# BaseBoard.net
KiCad netlist of a schematic drawn in EAGLE
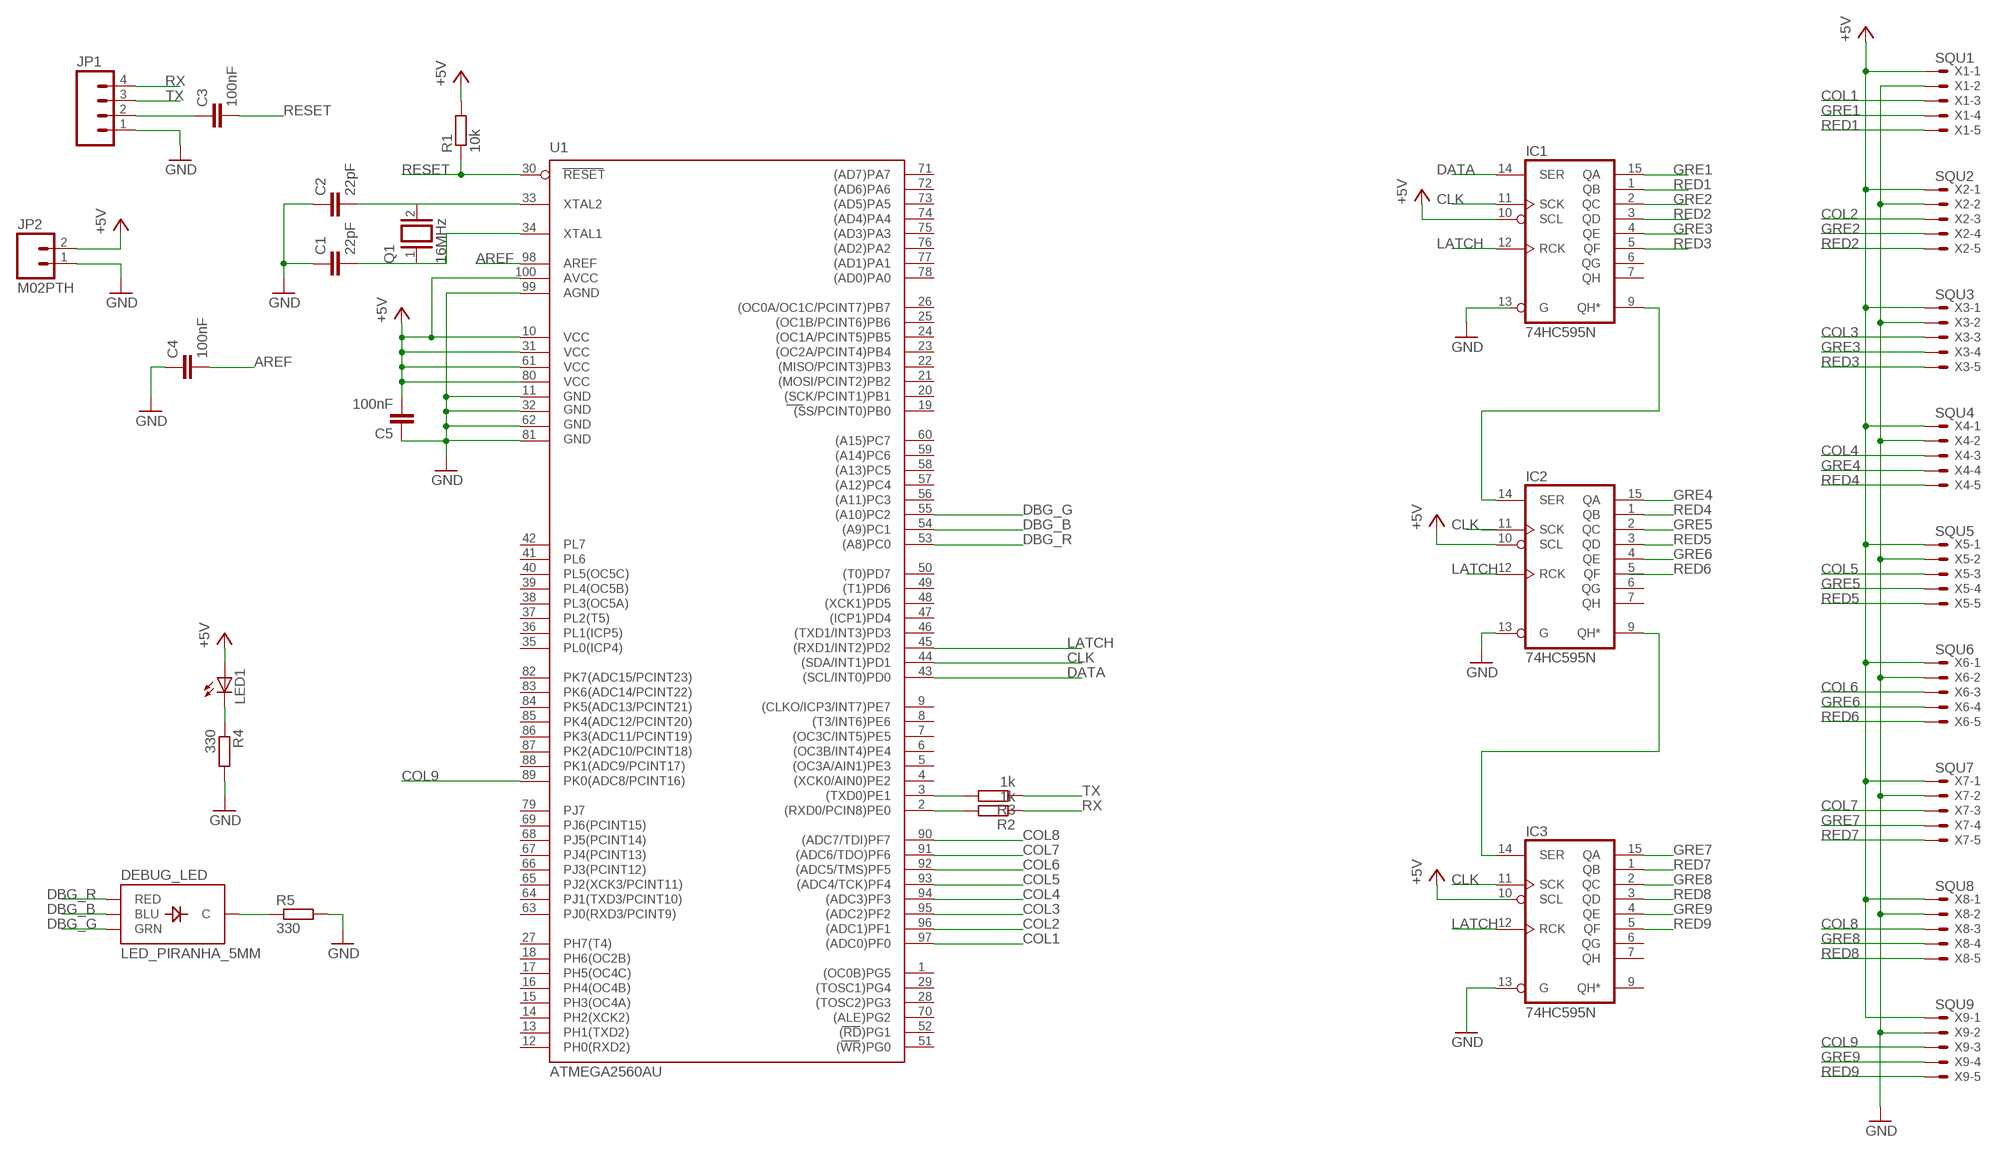
[diagram p0: schematic, sheet 1]

(export (version "E")
  (design (tool "Eeschema 10.0.6"))
  (components
    (comp (ref "C1")
      (value "22pF")
      (footprint "eagle-import:C5B2.5")
      (libsource (lib "eagle-import") (part "C5/2.5"))
    )
    (comp (ref "C2")
      (value "22pF")
      (footprint "eagle-import:C5B2.5")
      (libsource (lib "eagle-import") (part "C5/2.5"))
    )
    (comp (ref "C3")
      (value "100nF")
      (footprint "eagle-import:C5B3")
      (libsource (lib "eagle-import") (part "C5/3"))
    )
    (comp (ref "C4")
      (value "100nF")
      (footprint "eagle-import:C5B3")
      (libsource (lib "eagle-import") (part "C5/3"))
    )
    (comp (ref "C5")
      (value "100nF")
      (footprint "eagle-import:C5B3")
      (libsource (lib "eagle-import") (part "C5/3"))
    )
    (comp (ref "DEBUG_LED")
      (value "LED_PIRANHA_5MM")
      (footprint "eagle-import:LED_PIRANHA_5MM")
      (libsource (lib "eagle-import") (part "LED_PIRANHA_5MM"))
    )
    (comp (ref "IC1")
      (value "74HC595N")
      (footprint "eagle-import:DIL16")
      (libsource (lib "eagle-import") (part "74595NHC"))
    )
    (comp (ref "IC2")
      (value "74HC595N")
      (footprint "eagle-import:DIL16")
      (libsource (lib "eagle-import") (part "74595NHC"))
    )
    (comp (ref "IC3")
      (value "74HC595N")
      (footprint "eagle-import:DIL16")
      (libsource (lib "eagle-import") (part "74595NHC"))
    )
    (comp (ref "JP1")
      (value "M04PTH")
      (footprint "eagle-import:1X04")
      (libsource (lib "eagle-import") (part "M04PTH"))
    )
    (comp (ref "JP2")
      (value "M02PTH")
      (footprint "eagle-import:1X02")
      (libsource (lib "eagle-import") (part "M02PTH"))
    )
    (comp (ref "LED1")
      (value "LED3MM")
      (footprint "eagle-import:LED3MM")
      (libsource (lib "eagle-import") (part "LED3MM"))
    )
    (comp (ref "Q1")
      (value "16MHz")
      (footprint "eagle-import:QS")
      (libsource (lib "eagle-import") (part "XTAL/S"))
    )
    (comp (ref "R1")
      (value "10k")
      (footprint "eagle-import:0204_7")
      (libsource (lib "eagle-import") (part "R-EU_0204/7"))
    )
    (comp (ref "R2")
      (value "1k")
      (footprint "eagle-import:0204_7")
      (libsource (lib "eagle-import") (part "R-EU_0204/7"))
    )
    (comp (ref "R3")
      (value "1k")
      (footprint "eagle-import:0204_7")
      (libsource (lib "eagle-import") (part "R-EU_0204/7"))
    )
    (comp (ref "R4")
      (value "330")
      (footprint "eagle-import:0204_7")
      (libsource (lib "eagle-import") (part "R-EU_0204/7"))
    )
    (comp (ref "R5")
      (value "330")
      (footprint "eagle-import:0204_7")
      (libsource (lib "eagle-import") (part "R-EU_0204/7"))
    )
    (comp (ref "U1")
      (value "ATMEGA2560AU")
      (footprint "eagle-import:TQFP100")
      (libsource (lib "eagle-import") (part "ATMEGA2560AU"))
    )
    (comp (ref "X1")
      (value "SQU1")
      (footprint "eagle-import:53261-05")
      (libsource (lib "eagle-import") (part "53?-05261"))
    )
    (comp (ref "X2")
      (value "SQU2")
      (footprint "eagle-import:53261-05")
      (libsource (lib "eagle-import") (part "53?-05261"))
    )
    (comp (ref "X3")
      (value "SQU3")
      (footprint "eagle-import:53261-05")
      (libsource (lib "eagle-import") (part "53?-05261"))
    )
    (comp (ref "X4")
      (value "SQU4")
      (footprint "eagle-import:53261-05")
      (libsource (lib "eagle-import") (part "53?-05261"))
    )
    (comp (ref "X5")
      (value "SQU5")
      (footprint "eagle-import:53261-05")
      (libsource (lib "eagle-import") (part "53?-05261"))
    )
    (comp (ref "X6")
      (value "SQU6")
      (footprint "eagle-import:53261-05")
      (libsource (lib "eagle-import") (part "53?-05261"))
    )
    (comp (ref "X7")
      (value "SQU7")
      (footprint "eagle-import:53261-05")
      (libsource (lib "eagle-import") (part "53?-05261"))
    )
    (comp (ref "X8")
      (value "SQU8")
      (footprint "eagle-import:53261-05")
      (libsource (lib "eagle-import") (part "53?-05261"))
    )
    (comp (ref "X9")
      (value "SQU9")
      (footprint "eagle-import:53261-05")
      (libsource (lib "eagle-import") (part "53?-05261"))
    )
  )
  (nets
    (net (code "1") (name "+5V") (class "Default")
      (node (ref "C5") (pin "2") (pinfunction "2_2") (pintype "passive"))
      (node (ref "IC1") (pin "10") (pinfunction "SCL_10") (pintype "input"))
      (node (ref "IC2") (pin "10") (pinfunction "SCL_10") (pintype "input"))
      (node (ref "JP2") (pin "2") (pinfunction "2_2") (pintype "passive"))
      (node (ref "LED1") (pin "A") (pinfunction "A_A") (pintype "passive"))
      (node (ref "R1") (pin "2") (pinfunction "2_2") (pintype "passive"))
      (node (ref "U1") (pin "10") (pinfunction "VCC_10") (pintype "power_in"))
      (node (ref "U1") (pin "100") (pinfunction "AVCC_100") (pintype "power_in"))
      (node (ref "U1") (pin "31") (pinfunction "VCC1_31") (pintype "power_in"))
      (node (ref "U1") (pin "61") (pinfunction "VCC2_61") (pintype "power_in"))
      (node (ref "U1") (pin "80") (pinfunction "VCC3_80") (pintype "power_in"))
      (node (ref "X1") (pin "1") (pinfunction "S_1") (pintype "passive"))
      (node (ref "X2") (pin "1") (pinfunction "S_1") (pintype "passive"))
      (node (ref "X3") (pin "1") (pinfunction "S_1") (pintype "passive"))
      (node (ref "X4") (pin "1") (pinfunction "S_1") (pintype "passive"))
      (node (ref "X5") (pin "1") (pinfunction "S_1") (pintype "passive"))
      (node (ref "X6") (pin "1") (pinfunction "S_1") (pintype "passive"))
      (node (ref "X7") (pin "1") (pinfunction "S_1") (pintype "passive"))
      (node (ref "X8") (pin "1") (pinfunction "S_1") (pintype "passive"))
      (node (ref "X9") (pin "1") (pinfunction "S_1") (pintype "passive"))
    )
    (net (code "2") (name "/AREF") (class "Default")
      (node (ref "C4") (pin "2") (pinfunction "2_2") (pintype "passive"))
      (node (ref "U1") (pin "98") (pinfunction "AREF_98") (pintype "bidirectional"))
    )
    (net (code "3") (name "/CLK") (class "Default")
      (node (ref "IC1") (pin "11") (pinfunction "SCK_11") (pintype "input"))
      (node (ref "IC2") (pin "11") (pinfunction "SCK_11") (pintype "input"))
      (node (ref "IC3") (pin "11") (pinfunction "SCK_11") (pintype "input"))
      (node (ref "U1") (pin "44") (pinfunction "(SDA/INT1)PD1_44") (pintype "bidirectional"))
    )
    (net (code "4") (name "/COL1") (class "Default")
      (node (ref "U1") (pin "97") (pinfunction "(ADC0)PF0_97") (pintype "bidirectional"))
      (node (ref "X1") (pin "3") (pinfunction "S_3") (pintype "passive"))
    )
    (net (code "5") (name "/COL2") (class "Default")
      (node (ref "U1") (pin "96") (pinfunction "(ADC1)PF1_96") (pintype "bidirectional"))
      (node (ref "X2") (pin "3") (pinfunction "S_3") (pintype "passive"))
    )
    (net (code "6") (name "/COL3") (class "Default")
      (node (ref "U1") (pin "95") (pinfunction "(ADC2)PF2_95") (pintype "bidirectional"))
      (node (ref "X3") (pin "3") (pinfunction "S_3") (pintype "passive"))
    )
    (net (code "7") (name "/COL4") (class "Default")
      (node (ref "U1") (pin "94") (pinfunction "(ADC3)PF3_94") (pintype "bidirectional"))
      (node (ref "X4") (pin "3") (pinfunction "S_3") (pintype "passive"))
    )
    (net (code "8") (name "/COL5") (class "Default")
      (node (ref "U1") (pin "93") (pinfunction "(ADC4/TCK)PF4_93") (pintype "bidirectional"))
      (node (ref "X5") (pin "3") (pinfunction "S_3") (pintype "passive"))
    )
    (net (code "9") (name "/COL6") (class "Default")
      (node (ref "U1") (pin "92") (pinfunction "(ADC5/TMS)PF5_92") (pintype "bidirectional"))
      (node (ref "X6") (pin "3") (pinfunction "S_3") (pintype "passive"))
    )
    (net (code "10") (name "/COL7") (class "Default")
      (node (ref "U1") (pin "91") (pinfunction "(ADC6/TDO)PF6_91") (pintype "bidirectional"))
      (node (ref "X7") (pin "3") (pinfunction "S_3") (pintype "passive"))
    )
    (net (code "11") (name "/COL8") (class "Default")
      (node (ref "U1") (pin "90") (pinfunction "(ADC7/TDI)PF7_90") (pintype "bidirectional"))
      (node (ref "X8") (pin "3") (pinfunction "S_3") (pintype "passive"))
    )
    (net (code "12") (name "/COL9") (class "Default")
      (node (ref "U1") (pin "89") (pinfunction "PK0(ADC8/PCINT16)_89") (pintype "bidirectional"))
      (node (ref "X9") (pin "3") (pinfunction "S_3") (pintype "passive"))
    )
    (net (code "13") (name "/DATA") (class "Default")
      (node (ref "IC1") (pin "14") (pinfunction "SER_14") (pintype "input"))
      (node (ref "U1") (pin "43") (pinfunction "(SCL/INT0)PD0_43") (pintype "bidirectional"))
    )
    (net (code "14") (name "/DBG_B") (class "Default")
      (node (ref "DEBUG_LED") (pin "B") (pinfunction "BLU_B") (pintype "bidirectional"))
      (node (ref "U1") (pin "54") (pinfunction "(A9)PC1_54") (pintype "bidirectional"))
    )
    (net (code "15") (name "/DBG_G") (class "Default")
      (node (ref "DEBUG_LED") (pin "G") (pinfunction "GRN_G") (pintype "bidirectional"))
      (node (ref "U1") (pin "55") (pinfunction "(A10)PC2_55") (pintype "bidirectional"))
    )
    (net (code "16") (name "/DBG_R") (class "Default")
      (node (ref "DEBUG_LED") (pin "R") (pinfunction "RED_R") (pintype "bidirectional"))
      (node (ref "U1") (pin "53") (pinfunction "(A8)PC0_53") (pintype "bidirectional"))
    )
    (net (code "17") (name "/GRE1") (class "Default")
      (node (ref "IC1") (pin "15") (pinfunction "QA_15") (pintype "tri_state"))
      (node (ref "X1") (pin "4") (pinfunction "S_4") (pintype "passive"))
    )
    (net (code "18") (name "/GRE2") (class "Default")
      (node (ref "IC1") (pin "2") (pinfunction "QC_2") (pintype "tri_state"))
      (node (ref "X2") (pin "4") (pinfunction "S_4") (pintype "passive"))
    )
    (net (code "19") (name "/GRE3") (class "Default")
      (node (ref "IC1") (pin "4") (pinfunction "QE_4") (pintype "tri_state"))
      (node (ref "X3") (pin "4") (pinfunction "S_4") (pintype "passive"))
    )
    (net (code "20") (name "/GRE4") (class "Default")
      (node (ref "IC2") (pin "15") (pinfunction "QA_15") (pintype "tri_state"))
      (node (ref "X4") (pin "4") (pinfunction "S_4") (pintype "passive"))
    )
    (net (code "21") (name "/GRE5") (class "Default")
      (node (ref "IC2") (pin "2") (pinfunction "QC_2") (pintype "tri_state"))
      (node (ref "X5") (pin "4") (pinfunction "S_4") (pintype "passive"))
    )
    (net (code "22") (name "/GRE6") (class "Default")
      (node (ref "IC2") (pin "4") (pinfunction "QE_4") (pintype "tri_state"))
      (node (ref "X6") (pin "4") (pinfunction "S_4") (pintype "passive"))
    )
    (net (code "23") (name "/GRE7") (class "Default")
      (node (ref "IC3") (pin "15") (pinfunction "QA_15") (pintype "tri_state"))
      (node (ref "X7") (pin "4") (pinfunction "S_4") (pintype "passive"))
    )
    (net (code "24") (name "/GRE8") (class "Default")
      (node (ref "IC3") (pin "2") (pinfunction "QC_2") (pintype "tri_state"))
      (node (ref "X8") (pin "4") (pinfunction "S_4") (pintype "passive"))
    )
    (net (code "25") (name "/GRE9") (class "Default")
      (node (ref "IC3") (pin "4") (pinfunction "QE_4") (pintype "tri_state"))
      (node (ref "X9") (pin "4") (pinfunction "S_4") (pintype "passive"))
    )
    (net (code "26") (name "/LATCH") (class "Default")
      (node (ref "IC1") (pin "12") (pinfunction "RCK_12") (pintype "input"))
      (node (ref "IC2") (pin "12") (pinfunction "RCK_12") (pintype "input"))
      (node (ref "IC3") (pin "12") (pinfunction "RCK_12") (pintype "input"))
      (node (ref "U1") (pin "45") (pinfunction "(RXD1/INT2)PD2_45") (pintype "bidirectional"))
    )
    (net (code "27") (name "/RED1") (class "Default")
      (node (ref "IC1") (pin "1") (pinfunction "QB_1") (pintype "tri_state"))
      (node (ref "X1") (pin "5") (pinfunction "S_5") (pintype "passive"))
    )
    (net (code "28") (name "/RED2") (class "Default")
      (node (ref "IC1") (pin "3") (pinfunction "QD_3") (pintype "tri_state"))
      (node (ref "X2") (pin "5") (pinfunction "S_5") (pintype "passive"))
    )
    (net (code "29") (name "/RED3") (class "Default")
      (node (ref "IC1") (pin "5") (pinfunction "QF_5") (pintype "tri_state"))
      (node (ref "X3") (pin "5") (pinfunction "S_5") (pintype "passive"))
    )
    (net (code "30") (name "/RED4") (class "Default")
      (node (ref "IC2") (pin "1") (pinfunction "QB_1") (pintype "tri_state"))
      (node (ref "X4") (pin "5") (pinfunction "S_5") (pintype "passive"))
    )
    (net (code "31") (name "/RED5") (class "Default")
      (node (ref "IC2") (pin "3") (pinfunction "QD_3") (pintype "tri_state"))
      (node (ref "X5") (pin "5") (pinfunction "S_5") (pintype "passive"))
    )
    (net (code "32") (name "/RED6") (class "Default")
      (node (ref "X6") (pin "5") (pinfunction "S_5") (pintype "passive"))
    )
    (net (code "33") (name "/RED7") (class "Default")
      (node (ref "IC3") (pin "1") (pinfunction "QB_1") (pintype "tri_state"))
      (node (ref "X7") (pin "5") (pinfunction "S_5") (pintype "passive"))
    )
    (net (code "34") (name "/RED8") (class "Default")
      (node (ref "IC3") (pin "3") (pinfunction "QD_3") (pintype "tri_state"))
      (node (ref "X8") (pin "5") (pinfunction "S_5") (pintype "passive"))
    )
    (net (code "35") (name "/RED9") (class "Default")
      (node (ref "IC3") (pin "5") (pinfunction "QF_5") (pintype "tri_state"))
      (node (ref "X9") (pin "5") (pinfunction "S_5") (pintype "passive"))
    )
    (net (code "36") (name "/RESET") (class "Default")
      (node (ref "C3") (pin "2") (pinfunction "2_2") (pintype "passive"))
      (node (ref "R1") (pin "1") (pinfunction "1_1") (pintype "passive"))
      (node (ref "U1") (pin "30") (pinfunction "RESET_30") (pintype "input"))
    )
    (net (code "37") (name "/RX") (class "Default")
      (node (ref "JP1") (pin "4") (pinfunction "4_4") (pintype "passive"))
      (node (ref "R2") (pin "1") (pinfunction "1_1") (pintype "passive"))
    )
    (net (code "38") (name "/TX") (class "Default")
      (node (ref "JP1") (pin "3") (pinfunction "3_3") (pintype "passive"))
      (node (ref "R3") (pin "1") (pinfunction "1_1") (pintype "passive"))
    )
    (net (code "39") (name "GND") (class "Default")
      (node (ref "C1") (pin "1") (pinfunction "1_1") (pintype "passive"))
      (node (ref "C2") (pin "1") (pinfunction "1_1") (pintype "passive"))
      (node (ref "C4") (pin "1") (pinfunction "1_1") (pintype "passive"))
      (node (ref "C5") (pin "1") (pinfunction "1_1") (pintype "passive"))
      (node (ref "IC2") (pin "13") (pinfunction "G_13") (pintype "input"))
      (node (ref "JP1") (pin "1") (pinfunction "1_1") (pintype "passive"))
      (node (ref "JP2") (pin "1") (pinfunction "1_1") (pintype "passive"))
      (node (ref "R4") (pin "2") (pinfunction "2_2") (pintype "passive"))
      (node (ref "R5") (pin "2") (pinfunction "2_2") (pintype "passive"))
      (node (ref "U1") (pin "11") (pinfunction "GND_11") (pintype "power_in"))
      (node (ref "U1") (pin "32") (pinfunction "GND1_32") (pintype "power_in"))
      (node (ref "U1") (pin "62") (pinfunction "GND2_62") (pintype "power_in"))
      (node (ref "U1") (pin "81") (pinfunction "GND3_81") (pintype "power_in"))
      (node (ref "U1") (pin "99") (pinfunction "AGND_99") (pintype "power_in"))
      (node (ref "X1") (pin "2") (pinfunction "S_2") (pintype "passive"))
      (node (ref "X2") (pin "2") (pinfunction "S_2") (pintype "passive"))
      (node (ref "X3") (pin "2") (pinfunction "S_2") (pintype "passive"))
      (node (ref "X4") (pin "2") (pinfunction "S_2") (pintype "passive"))
      (node (ref "X5") (pin "2") (pinfunction "S_2") (pintype "passive"))
      (node (ref "X6") (pin "2") (pinfunction "S_2") (pintype "passive"))
      (node (ref "X7") (pin "2") (pinfunction "S_2") (pintype "passive"))
      (node (ref "X8") (pin "2") (pinfunction "S_2") (pintype "passive"))
      (node (ref "X9") (pin "2") (pinfunction "S_2") (pintype "passive"))
    )
    (net (code "40") (name "Net-(C3-Pad1)") (class "Default")
      (node (ref "C3") (pin "1") (pinfunction "1_1") (pintype "passive"))
      (node (ref "JP1") (pin "2") (pinfunction "2_2") (pintype "passive"))
    )
    (net (code "41") (name "Net-(DEBUG_LED-C)") (class "Default")
      (node (ref "DEBUG_LED") (pin "-") (pinfunction "C_-") (pintype "bidirectional"))
      (node (ref "R5") (pin "1") (pinfunction "1_1") (pintype "passive"))
    )
    (net (code "42") (name "Net-(IC1A-QH*)") (class "Default")
      (node (ref "IC1") (pin "9") (pinfunction "QH*_9") (pintype "tri_state"))
      (node (ref "IC2") (pin "14") (pinfunction "SER_14") (pintype "input"))
    )
    (net (code "43") (name "Net-(IC2A-QH*)") (class "Default")
      (node (ref "IC2") (pin "9") (pinfunction "QH*_9") (pintype "tri_state"))
      (node (ref "IC3") (pin "14") (pinfunction "SER_14") (pintype "input"))
    )
    (net (code "44") (name "Net-(LED1-C)") (class "Default")
      (node (ref "LED1") (pin "K") (pinfunction "C_K") (pintype "passive"))
      (node (ref "R4") (pin "1") (pinfunction "1_1") (pintype "passive"))
    )
    (net (code "45") (name "Net-(U1-(RXD0{slash}PCIN8)PE0)") (class "Default")
      (node (ref "R2") (pin "2") (pinfunction "2_2") (pintype "passive"))
      (node (ref "U1") (pin "2") (pinfunction "(RXD0/PCIN8)PE0_2") (pintype "bidirectional"))
    )
    (net (code "46") (name "Net-(U1-(TXD0)PE1)") (class "Default")
      (node (ref "R3") (pin "2") (pinfunction "2_2") (pintype "passive"))
      (node (ref "U1") (pin "3") (pinfunction "(TXD0)PE1_3") (pintype "bidirectional"))
    )
    (net (code "47") (name "Net-(U1-XTAL1)") (class "Default")
      (node (ref "C1") (pin "2") (pinfunction "2_2") (pintype "passive"))
      (node (ref "U1") (pin "34") (pinfunction "XTAL1_34") (pintype "input"))
    )
    (net (code "48") (name "Net-(U1-XTAL2)") (class "Default")
      (node (ref "C2") (pin "2") (pinfunction "2_2") (pintype "passive"))
      (node (ref "Q1") (pin "2") (pinfunction "2_2") (pintype "passive"))
      (node (ref "U1") (pin "33") (pinfunction "XTAL2_33") (pintype "output"))
    )
    (net (code "49") (name "unconnected-(IC1A-G-Pad13)") (class "Default")
      (node (ref "IC1") (pin "13") (pinfunction "G_13") (pintype "input"))
    )
    (net (code "50") (name "unconnected-(IC1A-QG-Pad6)") (class "Default")
      (node (ref "IC1") (pin "6") (pinfunction "QG_6") (pintype "tri_state"))
    )
    (net (code "51") (name "unconnected-(IC1A-QH-Pad7)") (class "Default")
      (node (ref "IC1") (pin "7") (pinfunction "QH_7") (pintype "tri_state"))
    )
    (net (code "52") (name "unconnected-(IC2A-QF-Pad5)") (class "Default")
      (node (ref "IC2") (pin "5") (pinfunction "QF_5") (pintype "tri_state"))
    )
    (net (code "53") (name "unconnected-(IC2A-QG-Pad6)") (class "Default")
      (node (ref "IC2") (pin "6") (pinfunction "QG_6") (pintype "tri_state"))
    )
    (net (code "54") (name "unconnected-(IC2A-QH-Pad7)") (class "Default")
      (node (ref "IC2") (pin "7") (pinfunction "QH_7") (pintype "tri_state"))
    )
    (net (code "55") (name "unconnected-(IC3A-G-Pad13)") (class "Default")
      (node (ref "IC3") (pin "13") (pinfunction "G_13") (pintype "input"))
    )
    (net (code "56") (name "unconnected-(IC3A-QG-Pad6)") (class "Default")
      (node (ref "IC3") (pin "6") (pinfunction "QG_6") (pintype "tri_state"))
    )
    (net (code "57") (name "unconnected-(IC3A-QH*-Pad9)") (class "Default")
      (node (ref "IC3") (pin "9") (pinfunction "QH*_9") (pintype "tri_state"))
    )
    (net (code "58") (name "unconnected-(IC3A-QH-Pad7)") (class "Default")
      (node (ref "IC3") (pin "7") (pinfunction "QH_7") (pintype "tri_state"))
    )
    (net (code "59") (name "unconnected-(IC3A-SCL-Pad10)") (class "Default")
      (node (ref "IC3") (pin "10") (pinfunction "SCL_10") (pintype "input"))
    )
    (net (code "60") (name "unconnected-(Q1-Pad1)") (class "Default")
      (node (ref "Q1") (pin "1") (pinfunction "1_1") (pintype "passive"))
    )
    (net (code "61") (name "unconnected-(U1-(A11)PC3-Pad56)") (class "Default")
      (node (ref "U1") (pin "56") (pinfunction "(A11)PC3_56") (pintype "bidirectional"))
    )
    (net (code "62") (name "unconnected-(U1-(A12)PC4-Pad57)") (class "Default")
      (node (ref "U1") (pin "57") (pinfunction "(A12)PC4_57") (pintype "bidirectional"))
    )
    (net (code "63") (name "unconnected-(U1-(A13)PC5-Pad58)") (class "Default")
      (node (ref "U1") (pin "58") (pinfunction "(A13)PC5_58") (pintype "bidirectional"))
    )
    (net (code "64") (name "unconnected-(U1-(A14)PC6-Pad59)") (class "Default")
      (node (ref "U1") (pin "59") (pinfunction "(A14)PC6_59") (pintype "bidirectional"))
    )
    (net (code "65") (name "unconnected-(U1-(A15)PC7-Pad60)") (class "Default")
      (node (ref "U1") (pin "60") (pinfunction "(A15)PC7_60") (pintype "bidirectional"))
    )
    (net (code "66") (name "unconnected-(U1-(AD0)PA0-Pad78)") (class "Default")
      (node (ref "U1") (pin "78") (pinfunction "(AD0)PA0_78") (pintype "bidirectional"))
    )
    (net (code "67") (name "unconnected-(U1-(AD1)PA1-Pad77)") (class "Default")
      (node (ref "U1") (pin "77") (pinfunction "(AD1)PA1_77") (pintype "bidirectional"))
    )
    (net (code "68") (name "unconnected-(U1-(AD2)PA2-Pad76)") (class "Default")
      (node (ref "U1") (pin "76") (pinfunction "(AD2)PA2_76") (pintype "bidirectional"))
    )
    (net (code "69") (name "unconnected-(U1-(AD3)PA3-Pad75)") (class "Default")
      (node (ref "U1") (pin "75") (pinfunction "(AD3)PA3_75") (pintype "bidirectional"))
    )
    (net (code "70") (name "unconnected-(U1-(AD4)PA4-Pad74)") (class "Default")
      (node (ref "U1") (pin "74") (pinfunction "(AD4)PA4_74") (pintype "bidirectional"))
    )
    (net (code "71") (name "unconnected-(U1-(AD5)PA5-Pad73)") (class "Default")
      (node (ref "U1") (pin "73") (pinfunction "(AD5)PA5_73") (pintype "bidirectional"))
    )
    (net (code "72") (name "unconnected-(U1-(AD6)PA6-Pad72)") (class "Default")
      (node (ref "U1") (pin "72") (pinfunction "(AD6)PA6_72") (pintype "bidirectional"))
    )
    (net (code "73") (name "unconnected-(U1-(AD7)PA7-Pad71)") (class "Default")
      (node (ref "U1") (pin "71") (pinfunction "(AD7)PA7_71") (pintype "bidirectional"))
    )
    (net (code "74") (name "unconnected-(U1-(ALE)PG2-Pad70)") (class "Default")
      (node (ref "U1") (pin "70") (pinfunction "(ALE)PG2_70") (pintype "bidirectional"))
    )
    (net (code "75") (name "unconnected-(U1-(CLKO{slash}ICP3{slash}INT7)PE7-Pad9)") (class "Default")
      (node (ref "U1") (pin "9") (pinfunction "(CLKO/ICP3/INT7)PE7_9") (pintype "bidirectional"))
    )
    (net (code "76") (name "unconnected-(U1-(ICP1)PD4-Pad47)") (class "Default")
      (node (ref "U1") (pin "47") (pinfunction "(ICP1)PD4_47") (pintype "bidirectional"))
    )
    (net (code "77") (name "unconnected-(U1-(MISO{slash}PCINT3)PB3-Pad22)") (class "Default")
      (node (ref "U1") (pin "22") (pinfunction "(MISO/PCINT3)PB3_22") (pintype "bidirectional"))
    )
    (net (code "78") (name "unconnected-(U1-(MOSI{slash}PCINT2)PB2-Pad21)") (class "Default")
      (node (ref "U1") (pin "21") (pinfunction "(MOSI/PCINT2)PB2_21") (pintype "bidirectional"))
    )
    (net (code "79") (name "unconnected-(U1-(OC0A{slash}OC1C{slash}PCINT7)PB7-Pad26)") (class "Default")
      (node (ref "U1") (pin "26") (pinfunction "(OC0A/OC1C/PCINT7)PB7_26") (pintype "bidirectional"))
    )
    (net (code "80") (name "unconnected-(U1-(OC0B)PG5-Pad1)") (class "Default")
      (node (ref "U1") (pin "1") (pinfunction "(OC0B)PG5_1") (pintype "bidirectional"))
    )
    (net (code "81") (name "unconnected-(U1-(OC1A{slash}PCINT5)PB5-Pad24)") (class "Default")
      (node (ref "U1") (pin "24") (pinfunction "(OC1A/PCINT5)PB5_24") (pintype "bidirectional"))
    )
    (net (code "82") (name "unconnected-(U1-(OC1B{slash}PCINT6)PB6-Pad25)") (class "Default")
      (node (ref "U1") (pin "25") (pinfunction "(OC1B/PCINT6)PB6_25") (pintype "bidirectional"))
    )
    (net (code "83") (name "unconnected-(U1-(OC2A{slash}PCINT4)PB4-Pad23)") (class "Default")
      (node (ref "U1") (pin "23") (pinfunction "(OC2A/PCINT4)PB4_23") (pintype "bidirectional"))
    )
    (net (code "84") (name "unconnected-(U1-(OC3A{slash}AIN1)PE3-Pad5)") (class "Default")
      (node (ref "U1") (pin "5") (pinfunction "(OC3A/AIN1)PE3_5") (pintype "bidirectional"))
    )
    (net (code "85") (name "unconnected-(U1-(OC3B{slash}INT4)PE4-Pad6)") (class "Default")
      (node (ref "U1") (pin "6") (pinfunction "(OC3B/INT4)PE4_6") (pintype "bidirectional"))
    )
    (net (code "86") (name "unconnected-(U1-(OC3C{slash}INT5)PE5-Pad7)") (class "Default")
      (node (ref "U1") (pin "7") (pinfunction "(OC3C/INT5)PE5_7") (pintype "bidirectional"))
    )
    (net (code "87") (name "unconnected-(U1-(RD)PG1-Pad52)") (class "Default")
      (node (ref "U1") (pin "52") (pinfunction "(RD)PG1_52") (pintype "bidirectional"))
    )
    (net (code "88") (name "unconnected-(U1-(SCK{slash}PCINT1)PB1-Pad20)") (class "Default")
      (node (ref "U1") (pin "20") (pinfunction "(SCK/PCINT1)PB1_20") (pintype "bidirectional"))
    )
    (net (code "89") (name "unconnected-(U1-(SS{slash}PCINT0)PB0-Pad19)") (class "Default")
      (node (ref "U1") (pin "19") (pinfunction "(SS/PCINT0)PB0_19") (pintype "bidirectional"))
    )
    (net (code "90") (name "unconnected-(U1-(T0)PD7-Pad50)") (class "Default")
      (node (ref "U1") (pin "50") (pinfunction "(T0)PD7_50") (pintype "bidirectional"))
    )
    (net (code "91") (name "unconnected-(U1-(T1)PD6-Pad49)") (class "Default")
      (node (ref "U1") (pin "49") (pinfunction "(T1)PD6_49") (pintype "bidirectional"))
    )
    (net (code "92") (name "unconnected-(U1-(T3{slash}INT6)PE6-Pad8)") (class "Default")
      (node (ref "U1") (pin "8") (pinfunction "(T3/INT6)PE6_8") (pintype "bidirectional"))
    )
    (net (code "93") (name "unconnected-(U1-(TOSC1)PG4-Pad29)") (class "Default")
      (node (ref "U1") (pin "29") (pinfunction "(TOSC1)PG4_29") (pintype "bidirectional"))
    )
    (net (code "94") (name "unconnected-(U1-(TOSC2)PG3-Pad28)") (class "Default")
      (node (ref "U1") (pin "28") (pinfunction "(TOSC2)PG3_28") (pintype "bidirectional"))
    )
    (net (code "95") (name "unconnected-(U1-(TXD1{slash}INT3)PD3-Pad46)") (class "Default")
      (node (ref "U1") (pin "46") (pinfunction "(TXD1/INT3)PD3_46") (pintype "bidirectional"))
    )
    (net (code "96") (name "unconnected-(U1-(WR)PG0-Pad51)") (class "Default")
      (node (ref "U1") (pin "51") (pinfunction "(WR)PG0_51") (pintype "bidirectional"))
    )
    (net (code "97") (name "unconnected-(U1-(XCK0{slash}AIN0)PE2-Pad4)") (class "Default")
      (node (ref "U1") (pin "4") (pinfunction "(XCK0/AIN0)PE2_4") (pintype "bidirectional"))
    )
    (net (code "98") (name "unconnected-(U1-(XCK1)PD5-Pad48)") (class "Default")
      (node (ref "U1") (pin "48") (pinfunction "(XCK1)PD5_48") (pintype "bidirectional"))
    )
    (net (code "99") (name "unconnected-(U1-PH0(RXD2)-Pad12)") (class "Default")
      (node (ref "U1") (pin "12") (pinfunction "PH0(RXD2)_12") (pintype "bidirectional"))
    )
    (net (code "100") (name "unconnected-(U1-PH1(TXD2)-Pad13)") (class "Default")
      (node (ref "U1") (pin "13") (pinfunction "PH1(TXD2)_13") (pintype "bidirectional"))
    )
    (net (code "101") (name "unconnected-(U1-PH2(XCK2)-Pad14)") (class "Default")
      (node (ref "U1") (pin "14") (pinfunction "PH2(XCK2)_14") (pintype "bidirectional"))
    )
    (net (code "102") (name "unconnected-(U1-PH3(OC4A)-Pad15)") (class "Default")
      (node (ref "U1") (pin "15") (pinfunction "PH3(OC4A)_15") (pintype "bidirectional"))
    )
    (net (code "103") (name "unconnected-(U1-PH4(OC4B)-Pad16)") (class "Default")
      (node (ref "U1") (pin "16") (pinfunction "PH4(OC4B)_16") (pintype "bidirectional"))
    )
    (net (code "104") (name "unconnected-(U1-PH5(OC4C)-Pad17)") (class "Default")
      (node (ref "U1") (pin "17") (pinfunction "PH5(OC4C)_17") (pintype "bidirectional"))
    )
    (net (code "105") (name "unconnected-(U1-PH6(OC2B)-Pad18)") (class "Default")
      (node (ref "U1") (pin "18") (pinfunction "PH6(OC2B)_18") (pintype "bidirectional"))
    )
    (net (code "106") (name "unconnected-(U1-PH7(T4)-Pad27)") (class "Default")
      (node (ref "U1") (pin "27") (pinfunction "PH7(T4)_27") (pintype "bidirectional"))
    )
    (net (code "107") (name "unconnected-(U1-PJ0(RXD3{slash}PCINT9)-Pad63)") (class "Default")
      (node (ref "U1") (pin "63") (pinfunction "PJ0(RXD3/PCINT9)_63") (pintype "bidirectional"))
    )
    (net (code "108") (name "unconnected-(U1-PJ1(TXD3{slash}PCINT10)-Pad64)") (class "Default")
      (node (ref "U1") (pin "64") (pinfunction "PJ1(TXD3/PCINT10)_64") (pintype "bidirectional"))
    )
    (net (code "109") (name "unconnected-(U1-PJ2(XCK3{slash}PCINT11)-Pad65)") (class "Default")
      (node (ref "U1") (pin "65") (pinfunction "PJ2(XCK3/PCINT11)_65") (pintype "bidirectional"))
    )
    (net (code "110") (name "unconnected-(U1-PJ3(PCINT12)-Pad66)") (class "Default")
      (node (ref "U1") (pin "66") (pinfunction "PJ3(PCINT12)_66") (pintype "bidirectional"))
    )
    (net (code "111") (name "unconnected-(U1-PJ4(PCINT13)-Pad67)") (class "Default")
      (node (ref "U1") (pin "67") (pinfunction "PJ4(PCINT13)_67") (pintype "bidirectional"))
    )
    (net (code "112") (name "unconnected-(U1-PJ5(PCINT14)-Pad68)") (class "Default")
      (node (ref "U1") (pin "68") (pinfunction "PJ5(PCINT14)_68") (pintype "bidirectional"))
    )
    (net (code "113") (name "unconnected-(U1-PJ6(PCINT15)-Pad69)") (class "Default")
      (node (ref "U1") (pin "69") (pinfunction "PJ6(PCINT15)_69") (pintype "bidirectional"))
    )
    (net (code "114") (name "unconnected-(U1-PJ7-Pad79)") (class "Default")
      (node (ref "U1") (pin "79") (pinfunction "PJ7_79") (pintype "bidirectional"))
    )
    (net (code "115") (name "unconnected-(U1-PK1(ADC9{slash}PCINT17)-Pad88)") (class "Default")
      (node (ref "U1") (pin "88") (pinfunction "PK1(ADC9/PCINT17)_88") (pintype "bidirectional"))
    )
    (net (code "116") (name "unconnected-(U1-PK2(ADC10{slash}PCINT18)-Pad87)") (class "Default")
      (node (ref "U1") (pin "87") (pinfunction "PK2(ADC10/PCINT18)_87") (pintype "bidirectional"))
    )
    (net (code "117") (name "unconnected-(U1-PK3(ADC11{slash}PCINT19)-Pad86)") (class "Default")
      (node (ref "U1") (pin "86") (pinfunction "PK3(ADC11/PCINT19)_86") (pintype "bidirectional"))
    )
    (net (code "118") (name "unconnected-(U1-PK4(ADC12{slash}PCINT20)-Pad85)") (class "Default")
      (node (ref "U1") (pin "85") (pinfunction "PK4(ADC12/PCINT20)_85") (pintype "bidirectional"))
    )
    (net (code "119") (name "unconnected-(U1-PK5(ADC13{slash}PCINT21)-Pad84)") (class "Default")
      (node (ref "U1") (pin "84") (pinfunction "PK5(ADC13/PCINT21)_84") (pintype "bidirectional"))
    )
    (net (code "120") (name "unconnected-(U1-PK6(ADC14{slash}PCINT22)-Pad83)") (class "Default")
      (node (ref "U1") (pin "83") (pinfunction "PK6(ADC14/PCINT22)_83") (pintype "bidirectional"))
    )
    (net (code "121") (name "unconnected-(U1-PK7(ADC15{slash}PCINT23)-Pad82)") (class "Default")
      (node (ref "U1") (pin "82") (pinfunction "PK7(ADC15/PCINT23)_82") (pintype "bidirectional"))
    )
    (net (code "122") (name "unconnected-(U1-PL0(ICP4)-Pad35)") (class "Default")
      (node (ref "U1") (pin "35") (pinfunction "PL0(ICP4)_35") (pintype "bidirectional"))
    )
    (net (code "123") (name "unconnected-(U1-PL1(ICP5)-Pad36)") (class "Default")
      (node (ref "U1") (pin "36") (pinfunction "PL1(ICP5)_36") (pintype "bidirectional"))
    )
    (net (code "124") (name "unconnected-(U1-PL2(T5)-Pad37)") (class "Default")
      (node (ref "U1") (pin "37") (pinfunction "PL2(T5)_37") (pintype "bidirectional"))
    )
    (net (code "125") (name "unconnected-(U1-PL3(OC5A)-Pad38)") (class "Default")
      (node (ref "U1") (pin "38") (pinfunction "PL3(OC5A)_38") (pintype "bidirectional"))
    )
    (net (code "126") (name "unconnected-(U1-PL4(OC5B)-Pad39)") (class "Default")
      (node (ref "U1") (pin "39") (pinfunction "PL4(OC5B)_39") (pintype "bidirectional"))
    )
    (net (code "127") (name "unconnected-(U1-PL5(OC5C)-Pad40)") (class "Default")
      (node (ref "U1") (pin "40") (pinfunction "PL5(OC5C)_40") (pintype "bidirectional"))
    )
    (net (code "128") (name "unconnected-(U1-PL6-Pad41)") (class "Default")
      (node (ref "U1") (pin "41") (pinfunction "PL6_41") (pintype "bidirectional"))
    )
    (net (code "129") (name "unconnected-(U1-PL7-Pad42)") (class "Default")
      (node (ref "U1") (pin "42") (pinfunction "PL7_42") (pintype "bidirectional"))
    )
  )
)
